# PCB_DYBoard_Feeder_V2.net
KiCad netlist of a schematic drawn in Altium Designer
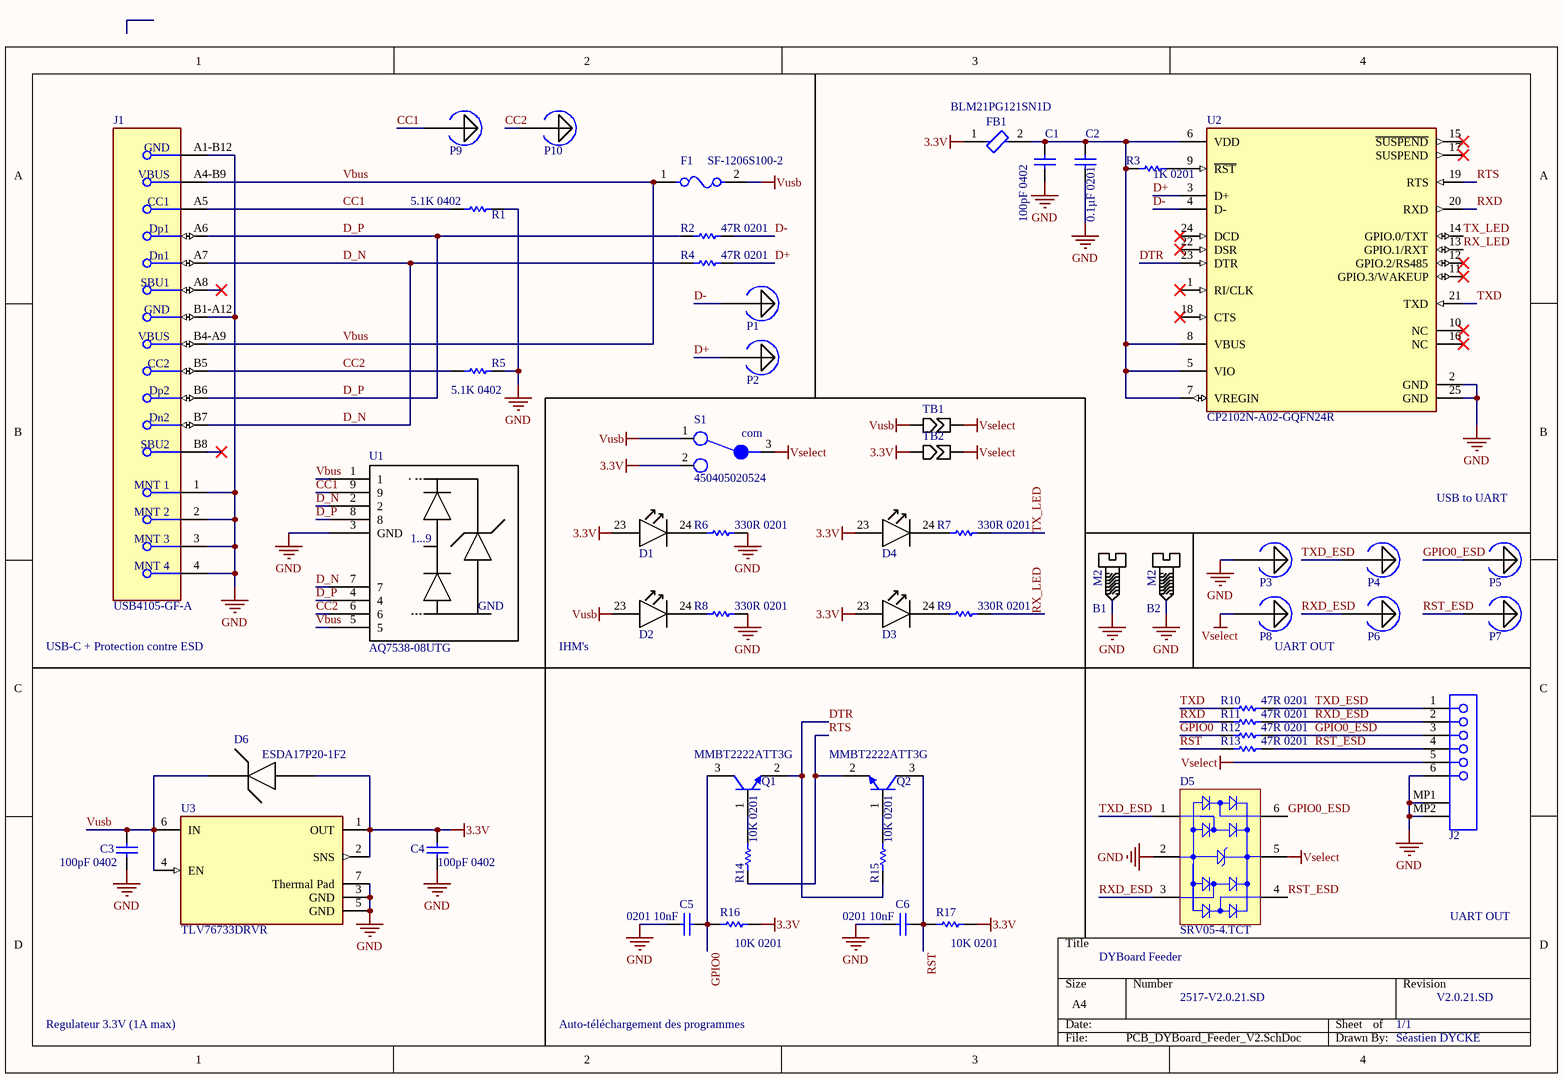
[diagram p0: PCB_DYBoard_Feeder_V2.SchDoc]

(export (version "E")
  (design (tool "Eeschema 10.0.6"))
  (components
    (comp (ref "B1")
      (value "bolt_M2")
      (footprint "bolt_M2")
      (libsource (lib "AQ7538-08UTG") (part "bolt_M2"))
    )
    (comp (ref "B2")
      (value "bolt_M2")
      (footprint "bolt_M2")
      (libsource (lib "AQ7538-08UTG") (part "bolt_M2"))
    )
    (comp (ref "C1")
      (value "100pF 0402")
      (footprint "0402")
      (description "Capacitor (Semiconductor SIM Model)")
      (fields (field (name "Comment") "Cap Semi") (field (name "PUBLISHER") "Altium Limited"))
      (libsource (lib "Miscellaneous Devices") (part "Cap Semi"))
    )
    (comp (ref "C2")
      (value "0.1µF 0201")
      (footprint "CAPC0603X33X15LL03T05")
      (fields
        (field (name "PART NUMBER") "02016D104KAT2A")
        (field (name "MANUFACTURER") "AVX Interconnect / Elco")
      )
      (libsource (lib "Altium Content Vault") (part "CAP"))
    )
    (comp (ref "C3")
      (value "100pF 0402")
      (footprint "0402")
      (description "Capacitor (Semiconductor SIM Model)")
      (fields (field (name "Comment") "Cap Semi") (field (name "PUBLISHER") "Altium Limited"))
      (libsource (lib "Miscellaneous Devices") (part "Cap Semi"))
    )
    (comp (ref "C4")
      (value "100pF 0402")
      (footprint "0402")
      (description "Capacitor (Semiconductor SIM Model)")
      (fields (field (name "Comment") "Cap Semi") (field (name "PUBLISHER") "Altium Limited"))
      (libsource (lib "Miscellaneous Devices") (part "Cap Semi"))
    )
    (comp (ref "C5")
      (value "0201 10nF")
      (footprint "CAPC0603X33X15LL03T05")
      (fields
        (field (name "PART NUMBER") "02016D104KAT2A")
        (field (name "MANUFACTURER") "AVX Interconnect / Elco")
      )
      (libsource (lib "Altium Content Vault") (part "CAP"))
    )
    (comp (ref "C6")
      (value "0201 10nF")
      (footprint "CAPC0603X33X15LL03T05")
      (fields
        (field (name "PART NUMBER") "02016D104KAT2A")
        (field (name "MANUFACTURER") "AVX Interconnect / Elco")
      )
      (libsource (lib "Altium Content Vault") (part "CAP"))
    )
    (comp (ref "D1")
      (value "LED_0402")
      (footprint "LED_0402")
      (libsource (lib "AQ7538-08UTG") (part "LED_0402"))
    )
    (comp (ref "D2")
      (value "LED_0402")
      (footprint "LED_0402")
      (libsource (lib "AQ7538-08UTG") (part "LED_0402"))
    )
    (comp (ref "D3")
      (value "LED_0402")
      (footprint "LED_0402")
      (libsource (lib "AQ7538-08UTG") (part "LED_0402"))
    )
    (comp (ref "D4")
      (value "LED_0402")
      (footprint "LED_0402")
      (libsource (lib "AQ7538-08UTG") (part "LED_0402"))
    )
    (comp (ref "D5")
      (value "SRV05-4.TCT")
      (footprint "SMTC-SOT23-6_V")
      (fields (field (name "MANUFACTURER") "Semtech"))
      (libsource (lib "Altium Content Vault") (part "STM-USB_DVI_HDMIULC6-4SC6X-SOT23-6L"))
    )
    (comp (ref "D6")
      (value "ESDA17P20-1F2")
      (footprint "ESDA17P20-1F2")
      (libsource (lib "AQ7538-08UTG") (part "ESDA17P20-1F2"))
    )
    (comp (ref "F1")
      (value "SF-1206S100-2")
      (footprint "FP-SF-1206S-MFG")
      (description "FUSE BOARD MOUNT 1A 63VDC 1206")
      (fields
        (field (name "MANUFACTURER") "Bourns Inc.")
        (field (name "OCTOPART") "https://octopart.com/sf-1206s100-2-bourns-8398337")
      )
      (libsource (lib "Altium Content Vault") (part "5bcf9b9f640e542cf0359d10258e979"))
    )
    (comp (ref "FB1")
      (value "BLM21PG121SN1D")
      (footprint "FP-BLM21-0_2-t0_85-e0_5-d-IPC_C")
      (description "Chip Ferrite Bead, 0805, 120Ω @ 100MHz, 0.03Ω, 25%, 3A")
      (fields (field (name "TOLERANCE") "25%"))
      (libsource (lib "Altium Content Vault") (part "5f30dd21d616792df468990f7003faa"))
    )
    (comp (ref "J1")
      (value "USB4105-GF-A")
      (footprint "FP-USB4105-GF-A-MFG")
      (description "CONN RCPT USB2.0 TYPEC 5A")
      (fields
        (field (name "MANUFACTURER") "GCT")
        (field (name "OCTOPART") "https://octopart.com/usb4105-gf-a-gct-106627878")
      )
      (libsource (lib "Altium Content Vault") (part "e7c17a616881a82b79941196b4bec10"))
    )
    (comp (ref "J2")
      (value "SEB_MOLeX_6p")
      (footprint "SEB_MOLeX_6p")
      (libsource (lib "AQ7538-08UTG") (part "SEB_MOLeX_6p"))
    )
    (comp (ref "P1")
      (value "solderPad")
      (footprint "solderPad_2")
      (libsource (lib "AQ7538-08UTG") (part "solderPad"))
    )
    (comp (ref "P2")
      (value "solderPad")
      (footprint "solderPad_2")
      (libsource (lib "AQ7538-08UTG") (part "solderPad"))
    )
    (comp (ref "P3")
      (value "solderPad")
      (footprint "solderPad_2")
      (libsource (lib "AQ7538-08UTG") (part "solderPad"))
    )
    (comp (ref "P4")
      (value "solderPad")
      (footprint "solderPad_2")
      (libsource (lib "AQ7538-08UTG") (part "solderPad"))
    )
    (comp (ref "P5")
      (value "solderPad")
      (footprint "solderPad_2")
      (libsource (lib "AQ7538-08UTG") (part "solderPad"))
    )
    (comp (ref "P6")
      (value "solderPad")
      (footprint "solderPad_2")
      (libsource (lib "AQ7538-08UTG") (part "solderPad"))
    )
    (comp (ref "P7")
      (value "solderPad")
      (footprint "solderPad_2")
      (libsource (lib "AQ7538-08UTG") (part "solderPad"))
    )
    (comp (ref "P8")
      (value "solderPad")
      (footprint "solderPad_2")
      (libsource (lib "AQ7538-08UTG") (part "solderPad"))
    )
    (comp (ref "P9")
      (value "solderPad")
      (footprint "solderPad_2")
      (libsource (lib "AQ7538-08UTG") (part "solderPad"))
    )
    (comp (ref "P10")
      (value "solderPad")
      (footprint "solderPad_2")
      (libsource (lib "AQ7538-08UTG") (part "solderPad"))
    )
    (comp (ref "Q1")
      (value "MMBT2222ATT3G")
      (footprint "ONSC-SC-75-3-463-01_V")
      (description "General Purpose Transistor, NPN Silicon, 3-Pin SC-75, Pb-Free, Tape and Reel")
      (fields (field (name "MANUFACTURER") "On Semiconductor"))
      (libsource (lib "Altium Content Vault") (part "ONSC-NPN-B1E2C3-3"))
    )
    (comp (ref "Q2")
      (value "MMBT2222ATT3G")
      (footprint "ONSC-SC-75-3-463-01_V")
      (description "General Purpose Transistor, NPN Silicon, 3-Pin SC-75, Pb-Free, Tape and Reel")
      (fields (field (name "MANUFACTURER") "On Semiconductor"))
      (libsource (lib "Altium Content Vault") (part "ONSC-NPN-B1E2C3-3"))
    )
    (comp (ref "R1")
      (value "5.1K 0402")
      (footprint "RESC1005X40X25NL05T10")
      (fields (field (name "PART NUMBER") "RC0402FR-071KL") (field (name "MANUFACTURER") "Yageo / Phycomp"))
      (libsource (lib "Altium Content Vault") (part "RES"))
    )
    (comp (ref "R2")
      (value "47R 0201")
      (footprint "RESC0603X26X15ML03T05")
      (fields (field (name "MANUFACTURER") "Panasonic") (field (name "PART NUMBER") "ERJ1GNF47R0C"))
      (libsource (lib "Altium Content Vault") (part "RES"))
    )
    (comp (ref "R3")
      (value "1K 0201")
      (footprint "RESC0603X26X15ML03T05")
      (fields (field (name "MANUFACTURER") "Panasonic") (field (name "PART NUMBER") "ERJ1GNF47R0C"))
      (libsource (lib "Altium Content Vault") (part "RES"))
    )
    (comp (ref "R4")
      (value "47R 0201")
      (footprint "RESC0603X26X15ML03T05")
      (fields (field (name "MANUFACTURER") "Panasonic") (field (name "PART NUMBER") "ERJ1GNF47R0C"))
      (libsource (lib "Altium Content Vault") (part "RES"))
    )
    (comp (ref "R5")
      (value "5.1K 0402")
      (footprint "RESC1005X40X25NL05T10")
      (fields (field (name "PART NUMBER") "RC0402FR-071KL") (field (name "MANUFACTURER") "Yageo / Phycomp"))
      (libsource (lib "Altium Content Vault") (part "RES"))
    )
    (comp (ref "R6")
      (value "330R 0201")
      (footprint "RESC0603X26X15ML03T05")
      (fields (field (name "MANUFACTURER") "Panasonic") (field (name "PART NUMBER") "ERJ1GNF47R0C"))
      (libsource (lib "Altium Content Vault") (part "RES"))
    )
    (comp (ref "R7")
      (value "330R 0201")
      (footprint "RESC0603X26X15ML03T05")
      (fields (field (name "MANUFACTURER") "Panasonic") (field (name "PART NUMBER") "ERJ1GNF47R0C"))
      (libsource (lib "Altium Content Vault") (part "RES"))
    )
    (comp (ref "R8")
      (value "330R 0201")
      (footprint "RESC0603X26X15ML03T05")
      (fields (field (name "MANUFACTURER") "Panasonic") (field (name "PART NUMBER") "ERJ1GNF47R0C"))
      (libsource (lib "Altium Content Vault") (part "RES"))
    )
    (comp (ref "R9")
      (value "330R 0201")
      (footprint "RESC0603X26X15ML03T05")
      (fields (field (name "MANUFACTURER") "Panasonic") (field (name "PART NUMBER") "ERJ1GNF47R0C"))
      (libsource (lib "Altium Content Vault") (part "RES"))
    )
    (comp (ref "R10")
      (value "47R 0201")
      (footprint "RESC0603X26X15ML03T05")
      (fields (field (name "MANUFACTURER") "Panasonic") (field (name "PART NUMBER") "ERJ1GNF47R0C"))
      (libsource (lib "Altium Content Vault") (part "RES"))
    )
    (comp (ref "R11")
      (value "47R 0201")
      (footprint "RESC0603X26X15ML03T05")
      (fields (field (name "MANUFACTURER") "Panasonic") (field (name "PART NUMBER") "ERJ1GNF47R0C"))
      (libsource (lib "Altium Content Vault") (part "RES"))
    )
    (comp (ref "R12")
      (value "47R 0201")
      (footprint "RESC0603X26X15ML03T05")
      (fields (field (name "MANUFACTURER") "Panasonic") (field (name "PART NUMBER") "ERJ1GNF47R0C"))
      (libsource (lib "Altium Content Vault") (part "RES"))
    )
    (comp (ref "R13")
      (value "47R 0201")
      (footprint "RESC0603X26X15ML03T05")
      (fields (field (name "MANUFACTURER") "Panasonic") (field (name "PART NUMBER") "ERJ1GNF47R0C"))
      (libsource (lib "Altium Content Vault") (part "RES"))
    )
    (comp (ref "R14")
      (value "10K 0201")
      (footprint "RESC0603X26X15ML03T05")
      (fields (field (name "MANUFACTURER") "Panasonic") (field (name "PART NUMBER") "ERJ1GNF47R0C"))
      (libsource (lib "Altium Content Vault") (part "RES"))
    )
    (comp (ref "R15")
      (value "10K 0201")
      (footprint "RESC0603X26X15ML03T05")
      (fields (field (name "MANUFACTURER") "Panasonic") (field (name "PART NUMBER") "ERJ1GNF47R0C"))
      (libsource (lib "Altium Content Vault") (part "RES"))
    )
    (comp (ref "R16")
      (value "10K 0201")
      (footprint "RESC0603X26X15ML03T05")
      (fields (field (name "MANUFACTURER") "Panasonic") (field (name "PART NUMBER") "ERJ1GNF47R0C"))
      (libsource (lib "Altium Content Vault") (part "RES"))
    )
    (comp (ref "R17")
      (value "10K 0201")
      (footprint "RESC0603X26X15ML03T05")
      (fields (field (name "MANUFACTURER") "Panasonic") (field (name "PART NUMBER") "ERJ1GNF47R0C"))
      (libsource (lib "Altium Content Vault") (part "RES"))
    )
    (comp (ref "S1")
      (value "450405020524")
      (footprint "450405020524")
      (description "SMT 8.7 X 3.0 MM MINI SLIDE SWIT")
      (fields (field (name "MF") "WÃ¼rth Elektronik"))
      (libsource (lib "450405020524") (part "450405020524"))
    )
    (comp (ref "TB1")
      (value "tin_bridge")
      (footprint "tin_bridge")
      (libsource (lib "AQ7538-08UTG") (part "tin_bridge"))
    )
    (comp (ref "TB2")
      (value "tin_bridge")
      (footprint "tin_bridge")
      (libsource (lib "AQ7538-08UTG") (part "tin_bridge"))
    )
    (comp (ref "U1")
      (value "AQ7538-08UTG")
      (footprint "PCBComponent_1")
      (libsource (lib "AQ7538-08UTG") (part "AQ7538-08UTG"))
    )
    (comp (ref "U2")
      (value "CP2102N-A02-GQFN24R")
      (footprint "FP-CP2102N-A02-GQFN24R-MFG")
      (description "IC USB TO UART BRIDGE QFN24")
      (libsource (lib "Altium Content Vault") (part "b0631adbfa5cc005b67568d56cca589"))
    )
    (comp (ref "U3")
      (value "TLV76733DRVR")
      (footprint "FP-DRV0006A-IPC_C")
      (description "VOLTAGE COMPARATOR")
      (libsource (lib "Altium Content Vault") (part "527f072e48108a7b9f646086bfc5874"))
    )
  )
  (nets
    (net (code "1") (name "/CC1") (class "Default")
      (node (ref "J1") (pin "A5") (pinfunction "CC1_A5") (pintype "power_in"))
      (node (ref "P9") (pin "20") (pinfunction "20_20") (pintype "passive"))
      (node (ref "R1") (pin "1") (pinfunction "1_1") (pintype "passive"))
      (node (ref "U1") (pin "9") (pinfunction "9_9") (pintype "passive"))
    )
    (net (code "2") (name "/CC2") (class "Default")
      (node (ref "J1") (pin "B5") (pinfunction "CC2_B5") (pintype "bidirectional"))
      (node (ref "P10") (pin "20") (pinfunction "20_20") (pintype "passive"))
      (node (ref "R5") (pin "1") (pinfunction "1_1") (pintype "passive"))
      (node (ref "U1") (pin "6") (pinfunction "6_6") (pintype "passive"))
    )
    (net (code "3") (name "/D+") (class "Default")
      (node (ref "P2") (pin "20") (pinfunction "20_20") (pintype "passive"))
      (node (ref "R4") (pin "2") (pinfunction "2_2") (pintype "passive"))
      (node (ref "U2") (pin "3") (pinfunction "D+_3") (pintype "passive"))
    )
    (net (code "4") (name "/D-") (class "Default")
      (node (ref "P1") (pin "20") (pinfunction "20_20") (pintype "passive"))
      (node (ref "R2") (pin "2") (pinfunction "2_2") (pintype "passive"))
      (node (ref "U2") (pin "4") (pinfunction "D-_4") (pintype "passive"))
    )
    (net (code "5") (name "/DTR") (class "Default")
      (node (ref "Q1") (pin "2") (pinfunction "E_2") (pintype "passive"))
      (node (ref "R15") (pin "2") (pinfunction "2_2") (pintype "passive"))
      (node (ref "U2") (pin "23") (pinfunction "DTR_23") (pintype "input"))
    )
    (net (code "6") (name "/D_N") (class "Default")
      (node (ref "J1") (pin "A7") (pinfunction "Dn1_A7") (pintype "bidirectional"))
      (node (ref "J1") (pin "B7") (pinfunction "Dn2_B7") (pintype "bidirectional"))
      (node (ref "R4") (pin "1") (pinfunction "1_1") (pintype "passive"))
      (node (ref "U1") (pin "2") (pinfunction "2_2") (pintype "passive"))
      (node (ref "U1") (pin "7") (pinfunction "7_7") (pintype "passive"))
    )
    (net (code "7") (name "/D_P") (class "Default")
      (node (ref "J1") (pin "A6") (pinfunction "Dp1_A6") (pintype "bidirectional"))
      (node (ref "J1") (pin "B6") (pinfunction "Dp2_B6") (pintype "bidirectional"))
      (node (ref "R2") (pin "1") (pinfunction "1_1") (pintype "passive"))
      (node (ref "U1") (pin "4") (pinfunction "4_4") (pintype "passive"))
      (node (ref "U1") (pin "8") (pinfunction "8_8") (pintype "passive"))
    )
    (net (code "8") (name "/GPIO0") (class "Default")
      (node (ref "C5") (pin "2") (pinfunction "2_2") (pintype "passive"))
      (node (ref "Q1") (pin "3") (pinfunction "C_3") (pintype "passive"))
      (node (ref "R12") (pin "1") (pinfunction "1_1") (pintype "passive"))
      (node (ref "R16") (pin "1") (pinfunction "1_1") (pintype "passive"))
    )
    (net (code "9") (name "/GPIO0_ESD") (class "Default")
      (node (ref "D5") (pin "6") (pinfunction "I/O_4_6") (pintype "passive"))
      (node (ref "J2") (pin "3") (pinfunction "3_3") (pintype "passive"))
      (node (ref "P5") (pin "20") (pinfunction "20_20") (pintype "passive"))
      (node (ref "R12") (pin "2") (pinfunction "2_2") (pintype "passive"))
    )
    (net (code "10") (name "/RST") (class "Default")
      (node (ref "C6") (pin "2") (pinfunction "2_2") (pintype "passive"))
      (node (ref "Q2") (pin "3") (pinfunction "C_3") (pintype "passive"))
      (node (ref "R13") (pin "1") (pinfunction "1_1") (pintype "passive"))
      (node (ref "R17") (pin "1") (pinfunction "1_1") (pintype "passive"))
    )
    (net (code "11") (name "/RST_ESD") (class "Default")
      (node (ref "D5") (pin "4") (pinfunction "I/O_3_4") (pintype "passive"))
      (node (ref "J2") (pin "4") (pinfunction "4_4") (pintype "passive"))
      (node (ref "P7") (pin "20") (pinfunction "20_20") (pintype "passive"))
      (node (ref "R13") (pin "2") (pinfunction "2_2") (pintype "passive"))
    )
    (net (code "12") (name "/RTS") (class "Default")
      (node (ref "Q2") (pin "2") (pinfunction "E_2") (pintype "passive"))
      (node (ref "R14") (pin "2") (pinfunction "2_2") (pintype "passive"))
      (node (ref "U2") (pin "19") (pinfunction "RTS_19") (pintype "input"))
    )
    (net (code "13") (name "/RXD") (class "Default")
      (node (ref "R11") (pin "1") (pinfunction "1_1") (pintype "passive"))
      (node (ref "U2") (pin "20") (pinfunction "RXD_20") (pintype "output"))
    )
    (net (code "14") (name "/RXD_ESD") (class "Default")
      (node (ref "D5") (pin "3") (pinfunction "I/O_2_3") (pintype "passive"))
      (node (ref "J2") (pin "2") (pinfunction "2_2") (pintype "passive"))
      (node (ref "P6") (pin "20") (pinfunction "20_20") (pintype "passive"))
      (node (ref "R11") (pin "2") (pinfunction "2_2") (pintype "passive"))
    )
    (net (code "15") (name "/RX_LED") (class "Default")
      (node (ref "R9") (pin "2") (pinfunction "2_2") (pintype "passive"))
      (node (ref "U2") (pin "13") (pinfunction "GPIO.1/RXT_13") (pintype "bidirectional"))
    )
    (net (code "16") (name "/TXD") (class "Default")
      (node (ref "R10") (pin "1") (pinfunction "1_1") (pintype "passive"))
      (node (ref "U2") (pin "21") (pinfunction "TXD_21") (pintype "input"))
    )
    (net (code "17") (name "/TXD_ESD") (class "Default")
      (node (ref "D5") (pin "1") (pinfunction "I/O_1_1") (pintype "passive"))
      (node (ref "J2") (pin "1") (pinfunction "1_1") (pintype "passive"))
      (node (ref "P4") (pin "20") (pinfunction "20_20") (pintype "passive"))
      (node (ref "R10") (pin "2") (pinfunction "2_2") (pintype "passive"))
    )
    (net (code "18") (name "/TX_LED") (class "Default")
      (node (ref "R7") (pin "2") (pinfunction "2_2") (pintype "passive"))
      (node (ref "U2") (pin "14") (pinfunction "GPIO.0/TXT_14") (pintype "bidirectional"))
    )
    (net (code "19") (name "/Vbus") (class "Default")
      (node (ref "F1") (pin "1") (pinfunction "1_1") (pintype "passive"))
      (node (ref "J1") (pin "A4-B9") (pinfunction "VBUS_A4-B9") (pintype "power_in"))
      (node (ref "J1") (pin "B4-A9") (pinfunction "VBUS_B4-A9") (pintype "bidirectional"))
      (node (ref "U1") (pin "1") (pinfunction "1_1") (pintype "passive"))
      (node (ref "U1") (pin "5") (pinfunction "5_5") (pintype "passive"))
    )
    (net (code "20") (name "3.3V") (class "Default")
      (node (ref "C4") (pin "2") (pinfunction "2_2") (pintype "passive"))
      (node (ref "D1") (pin "23") (pinfunction "23_23") (pintype "passive"))
      (node (ref "D3") (pin "23") (pinfunction "23_23") (pintype "passive"))
      (node (ref "D4") (pin "23") (pinfunction "23_23") (pintype "passive"))
      (node (ref "D6") (pin "18") (pinfunction "A_18") (pintype "passive"))
      (node (ref "FB1") (pin "1") (pinfunction "1_1") (pintype "passive"))
      (node (ref "R16") (pin "2") (pinfunction "2_2") (pintype "passive"))
      (node (ref "R17") (pin "2") (pinfunction "2_2") (pintype "passive"))
      (node (ref "S1") (pin "2") (pinfunction "2_2") (pintype "passive"))
      (node (ref "TB2") (pin "21") (pinfunction "21_21") (pintype "passive"))
      (node (ref "U3") (pin "1") (pinfunction "OUT_1") (pintype "passive"))
      (node (ref "U3") (pin "2") (pinfunction "SNS_2") (pintype "output"))
    )
    (net (code "21") (name "GND") (class "Default")
      (node (ref "B1") (pin "20") (pinfunction "20_20") (pintype "passive"))
      (node (ref "B2") (pin "20") (pinfunction "20_20") (pintype "passive"))
      (node (ref "C1") (pin "1") (pinfunction "1_1") (pintype "passive"))
      (node (ref "C2") (pin "1") (pinfunction "1_1") (pintype "passive"))
      (node (ref "C3") (pin "1") (pinfunction "1_1") (pintype "passive"))
      (node (ref "C4") (pin "1") (pinfunction "1_1") (pintype "passive"))
      (node (ref "C5") (pin "1") (pinfunction "1_1") (pintype "passive"))
      (node (ref "C6") (pin "1") (pinfunction "1_1") (pintype "passive"))
      (node (ref "D5") (pin "2") (pinfunction "GND_2") (pintype "passive"))
      (node (ref "J1") (pin "1") (pinfunction "MNT_1_1") (pintype "power_in"))
      (node (ref "J1") (pin "2") (pinfunction "MNT_2_2") (pintype "power_in"))
      (node (ref "J1") (pin "3") (pinfunction "MNT_3_3") (pintype "power_in"))
      (node (ref "J1") (pin "4") (pinfunction "MNT_4_4") (pintype "power_in"))
      (node (ref "J1") (pin "A1-B12") (pinfunction "GND_A1-B12") (pintype "power_in"))
      (node (ref "J1") (pin "B1-A12") (pinfunction "GND_B1-A12") (pintype "bidirectional"))
      (node (ref "J2") (pin "6") (pinfunction "6_6") (pintype "passive"))
      (node (ref "J2") (pin "MP1") (pinfunction "MP1_MP1") (pintype "passive"))
      (node (ref "J2") (pin "MP2") (pinfunction "MP2_MP2") (pintype "passive"))
      (node (ref "P3") (pin "20") (pinfunction "20_20") (pintype "passive"))
      (node (ref "R1") (pin "2") (pinfunction "2_2") (pintype "passive"))
      (node (ref "R5") (pin "2") (pinfunction "2_2") (pintype "passive"))
      (node (ref "R6") (pin "2") (pinfunction "2_2") (pintype "passive"))
      (node (ref "R8") (pin "2") (pinfunction "2_2") (pintype "passive"))
      (node (ref "U1") (pin "3") (pinfunction "GND_3") (pintype "passive"))
      (node (ref "U2") (pin "2") (pinfunction "GND_2") (pintype "power_in"))
      (node (ref "U2") (pin "25") (pinfunction "GND_25") (pintype "power_in"))
      (node (ref "U3") (pin "3") (pinfunction "GND_3") (pintype "power_in"))
      (node (ref "U3") (pin "5") (pinfunction "GND_5") (pintype "power_in"))
      (node (ref "U3") (pin "7") (pinfunction "Thermal_Pad_7") (pintype "passive"))
    )
    (net (code "22") (name "Net-(D1-Pad24)") (class "Default")
      (node (ref "D1") (pin "24") (pinfunction "24_24") (pintype "passive"))
      (node (ref "R6") (pin "1") (pinfunction "1_1") (pintype "passive"))
    )
    (net (code "23") (name "Net-(D2-Pad24)") (class "Default")
      (node (ref "D2") (pin "24") (pinfunction "24_24") (pintype "passive"))
      (node (ref "R8") (pin "1") (pinfunction "1_1") (pintype "passive"))
    )
    (net (code "24") (name "Net-(D3-Pad24)") (class "Default")
      (node (ref "D3") (pin "24") (pinfunction "24_24") (pintype "passive"))
      (node (ref "R9") (pin "1") (pinfunction "1_1") (pintype "passive"))
    )
    (net (code "25") (name "Net-(D4-Pad24)") (class "Default")
      (node (ref "D4") (pin "24") (pinfunction "24_24") (pintype "passive"))
      (node (ref "R7") (pin "1") (pinfunction "1_1") (pintype "passive"))
    )
    (net (code "26") (name "Net-(Q1-B)") (class "Default")
      (node (ref "Q1") (pin "1") (pinfunction "B_1") (pintype "passive"))
      (node (ref "R14") (pin "1") (pinfunction "1_1") (pintype "passive"))
    )
    (net (code "27") (name "Net-(Q2-B)") (class "Default")
      (node (ref "Q2") (pin "1") (pinfunction "B_1") (pintype "passive"))
      (node (ref "R15") (pin "1") (pinfunction "1_1") (pintype "passive"))
    )
    (net (code "28") (name "Net-(U2-VBUS)") (class "Default")
      (node (ref "C1") (pin "2") (pinfunction "2_2") (pintype "passive"))
      (node (ref "C2") (pin "2") (pinfunction "2_2") (pintype "passive"))
      (node (ref "FB1") (pin "2") (pinfunction "2_2") (pintype "passive"))
      (node (ref "R3") (pin "1") (pinfunction "1_1") (pintype "passive"))
      (node (ref "U2") (pin "5") (pinfunction "VIO_5") (pintype "power_in"))
      (node (ref "U2") (pin "6") (pinfunction "VDD_6") (pintype "power_in"))
      (node (ref "U2") (pin "7") (pinfunction "VREGIN_7") (pintype "bidirectional"))
      (node (ref "U2") (pin "8") (pinfunction "VBUS_8") (pintype "power_in"))
    )
    (net (code "29") (name "Net-(U2-~{RST})") (class "Default")
      (node (ref "R3") (pin "2") (pinfunction "2_2") (pintype "passive"))
      (node (ref "U2") (pin "9") (pinfunction "~{RST}_9") (pintype "input"))
    )
    (net (code "30") (name "Vselect") (class "Default")
      (node (ref "D5") (pin "5") (pinfunction "VBUS_5") (pintype "passive"))
      (node (ref "J2") (pin "5") (pinfunction "5_5") (pintype "passive"))
      (node (ref "P8") (pin "20") (pinfunction "20_20") (pintype "passive"))
      (node (ref "S1") (pin "3") (pinfunction "3_3") (pintype "passive"))
      (node (ref "TB1") (pin "22") (pinfunction "22_22") (pintype "passive"))
      (node (ref "TB2") (pin "22") (pinfunction "22_22") (pintype "passive"))
    )
    (net (code "31") (name "Vusb") (class "Default")
      (node (ref "C3") (pin "2") (pinfunction "2_2") (pintype "passive"))
      (node (ref "D2") (pin "23") (pinfunction "23_23") (pintype "passive"))
      (node (ref "D6") (pin "19") (pinfunction "K_19") (pintype "passive"))
      (node (ref "F1") (pin "2") (pinfunction "2_2") (pintype "passive"))
      (node (ref "S1") (pin "1") (pinfunction "1_1") (pintype "passive"))
      (node (ref "TB1") (pin "21") (pinfunction "21_21") (pintype "passive"))
      (node (ref "U3") (pin "4") (pinfunction "EN_4") (pintype "input"))
      (node (ref "U3") (pin "6") (pinfunction "IN_6") (pintype "power_in"))
    )
    (net (code "32") (name "unconnected-(J1-SBU1-PadA8)") (class "Default")
      (node (ref "J1") (pin "A8") (pinfunction "SBU1_A8") (pintype "bidirectional+no_connect"))
    )
    (net (code "33") (name "unconnected-(J1-SBU2-PadB8)") (class "Default")
      (node (ref "J1") (pin "B8") (pinfunction "SBU2_B8") (pintype "power_in+no_connect"))
    )
    (net (code "34") (name "unconnected-(U2-CTS-Pad18)") (class "Default")
      (node (ref "U2") (pin "18") (pinfunction "CTS_18") (pintype "input+no_connect"))
    )
    (net (code "35") (name "unconnected-(U2-DCD-Pad24)") (class "Default")
      (node (ref "U2") (pin "24") (pinfunction "DCD_24") (pintype "input+no_connect"))
    )
    (net (code "36") (name "unconnected-(U2-DSR-Pad22)") (class "Default")
      (node (ref "U2") (pin "22") (pinfunction "DSR_22") (pintype "input+no_connect"))
    )
    (net (code "37") (name "unconnected-(U2-GPIO.2{slash}RS485-Pad12)") (class "Default")
      (node (ref "U2") (pin "12") (pinfunction "GPIO.2/RS485_12") (pintype "bidirectional+no_connect"))
    )
    (net (code "38") (name "unconnected-(U2-GPIO.3{slash}WAKEUP-Pad11)") (class "Default")
      (node (ref "U2") (pin "11") (pinfunction "GPIO.3/WAKEUP_11") (pintype "bidirectional+no_connect"))
    )
    (net (code "39") (name "unconnected-(U2-NC-Pad10)") (class "Default")
      (node (ref "U2") (pin "10") (pinfunction "NC_10") (pintype "passive+no_connect"))
    )
    (net (code "40") (name "unconnected-(U2-NC-Pad16)") (class "Default")
      (node (ref "U2") (pin "16") (pinfunction "NC_16") (pintype "passive+no_connect"))
    )
    (net (code "41") (name "unconnected-(U2-RI{slash}CLK-Pad1)") (class "Default")
      (node (ref "U2") (pin "1") (pinfunction "RI/CLK_1") (pintype "input+no_connect"))
    )
    (net (code "42") (name "unconnected-(U2-SUSPEND-Pad17)") (class "Default")
      (node (ref "U2") (pin "17") (pinfunction "SUSPEND_17") (pintype "output+no_connect"))
    )
    (net (code "43") (name "unconnected-(U2-~{SUSPEND}-Pad15)") (class "Default")
      (node (ref "U2") (pin "15") (pinfunction "~{SUSPEND}_15") (pintype "output+no_connect"))
    )
  )
)
